# sensing.net
KiCad netlist of a schematic drawn in EAGLE
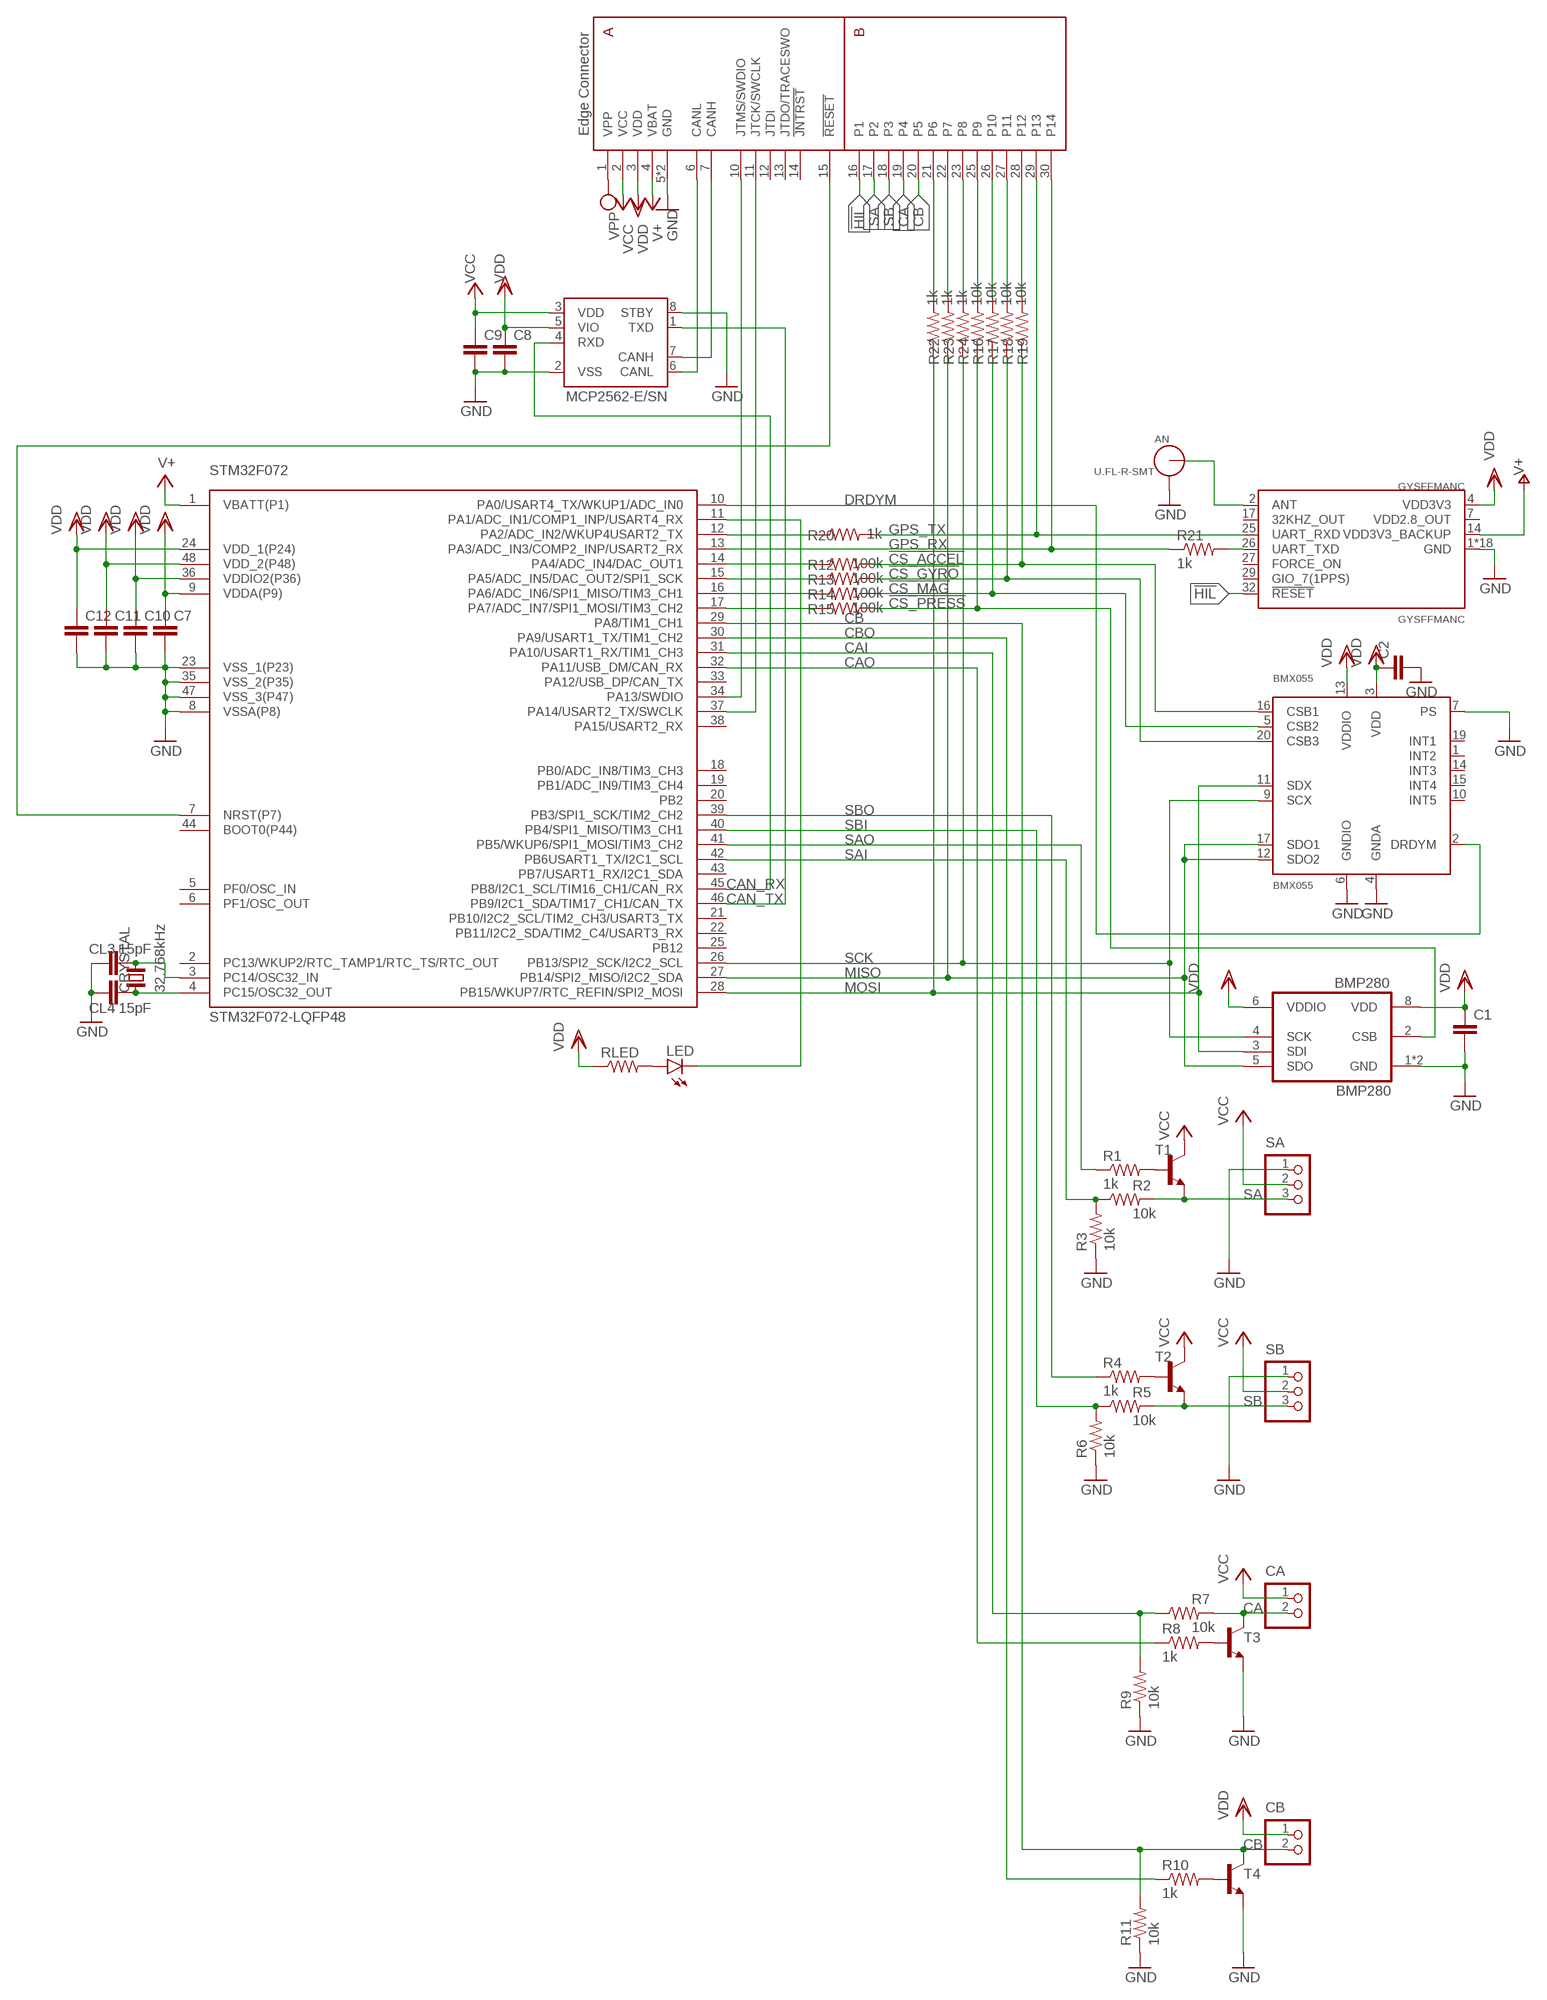
[diagram p0: schematic, sheet 1]

(export (version "E")
  (design (tool "Eeschema 10.0.6"))
  (components
    (comp (ref "AN")
      (value "U.FL-R-SMT")
      (footprint "eagle-import:U.FL_SMT")
      (fields (field (name "MANUFACTURER") "Hirose") (field (name "MPN") "U.FL-R-SMT-1(01)"))
      (libsource (lib "eagle-import") (part "U.FL-R-SMT"))
    )
    (comp (ref "BMP280")
      (value "BMP280")
      (footprint "eagle-import:BMP280")
      (libsource (lib "eagle-import") (part "BMP280"))
    )
    (comp (ref "BMX055")
      (value "BMX055")
      (footprint "eagle-import:BMX055")
      (fields (field (name "DIGI-KEY_PART_NUMBER") "828-1060-1-ND") (field (name "MF") "Bosch Sensortec"))
      (libsource (lib "eagle-import") (part "BMX055"))
    )
    (comp (ref "C1")
      (value "C-EUC0603K")
      (footprint "eagle-import:C0603K")
      (libsource (lib "eagle-import") (part "C-EUC0603K"))
    )
    (comp (ref "C2")
      (value "C-EUC0603K")
      (footprint "eagle-import:C0603K")
      (libsource (lib "eagle-import") (part "C-EUC0603K"))
    )
    (comp (ref "C7")
      (value "C-EUC0603K")
      (footprint "eagle-import:C0603K")
      (libsource (lib "eagle-import") (part "C-EUC0603K"))
    )
    (comp (ref "C8")
      (value "C-EUC0603K")
      (footprint "eagle-import:C0603K")
      (libsource (lib "eagle-import") (part "C-EUC0603K"))
    )
    (comp (ref "C9")
      (value "C-EUC0603K")
      (footprint "eagle-import:C0603K")
      (libsource (lib "eagle-import") (part "C-EUC0603K"))
    )
    (comp (ref "C10")
      (value "C-EUC0603K")
      (footprint "eagle-import:C0603K")
      (libsource (lib "eagle-import") (part "C-EUC0603K"))
    )
    (comp (ref "C11")
      (value "C-EUC0603K")
      (footprint "eagle-import:C0603K")
      (libsource (lib "eagle-import") (part "C-EUC0603K"))
    )
    (comp (ref "C12")
      (value "C-EUC0603K")
      (footprint "eagle-import:C0603K")
      (libsource (lib "eagle-import") (part "C-EUC0603K"))
    )
    (comp (ref "CA")
      (value "S2B-PH-K-S")
      (footprint "eagle-import:S2B-PH-K-S")
      (libsource (lib "eagle-import") (part "S2B-PH-K-S"))
    )
    (comp (ref "CB")
      (value "S2B-PH-K-S")
      (footprint "eagle-import:S2B-PH-K-S")
      (libsource (lib "eagle-import") (part "S2B-PH-K-S"))
    )
    (comp (ref "CL3")
      (value "15pF")
      (footprint "eagle-import:C0603K")
      (libsource (lib "eagle-import") (part "C-EUC0603K"))
    )
    (comp (ref "CL4")
      (value "15pF")
      (footprint "eagle-import:C0603K")
      (libsource (lib "eagle-import") (part "C-EUC0603K"))
    )
    (comp (ref "CRYSTAL")
      (value "32.768kHz")
      (footprint "eagle-import:FC-255")
      (libsource (lib "eagle-import") (part "CRYTALFC-255"))
    )
    (comp (ref "GYSFFMANC")
      (value "GYSFFMANC")
      (footprint "eagle-import:GYSFFMANC")
      (libsource (lib "eagle-import") (part "GYSFFMANC"))
    )
    (comp (ref "LED")
      (value "LEDCHIP-LED0603")
      (footprint "eagle-import:CHIP-LED0603")
      (libsource (lib "eagle-import") (part "LEDCHIP-LED0603"))
    )
    (comp (ref "MCP2562")
      (value "MCP2562-E/SN")
      (footprint "eagle-import:SOIC127P600X175-8N")
      (fields (field (name "MF") "Microchip"))
      (libsource (lib "eagle-import") (part "MCP2562-E/SN"))
    )
    (comp (ref "R1")
      (value "1k")
      (footprint "eagle-import:R0603")
      (libsource (lib "eagle-import") (part "resistor_348_R-US_R0603"))
    )
    (comp (ref "R2")
      (value "10k")
      (footprint "eagle-import:R0603")
      (libsource (lib "eagle-import") (part "resistor_348_R-US_R0603"))
    )
    (comp (ref "R3")
      (value "10k")
      (footprint "eagle-import:R0603")
      (libsource (lib "eagle-import") (part "resistor_348_R-US_R0603"))
    )
    (comp (ref "R4")
      (value "1k")
      (footprint "eagle-import:R0603")
      (libsource (lib "eagle-import") (part "resistor_348_R-US_R0603"))
    )
    (comp (ref "R5")
      (value "10k")
      (footprint "eagle-import:R0603")
      (libsource (lib "eagle-import") (part "resistor_348_R-US_R0603"))
    )
    (comp (ref "R6")
      (value "10k")
      (footprint "eagle-import:R0603")
      (libsource (lib "eagle-import") (part "resistor_348_R-US_R0603"))
    )
    (comp (ref "R7")
      (value "10k")
      (footprint "eagle-import:R0603")
      (libsource (lib "eagle-import") (part "resistor_348_R-US_R0603"))
    )
    (comp (ref "R8")
      (value "1k")
      (footprint "eagle-import:R0603")
      (libsource (lib "eagle-import") (part "resistor_348_R-US_R0603"))
    )
    (comp (ref "R9")
      (value "10k")
      (footprint "eagle-import:R0603")
      (libsource (lib "eagle-import") (part "resistor_348_R-US_R0603"))
    )
    (comp (ref "R10")
      (value "1k")
      (footprint "eagle-import:R0603")
      (libsource (lib "eagle-import") (part "resistor_348_R-US_R0603"))
    )
    (comp (ref "R11")
      (value "10k")
      (footprint "eagle-import:R0603")
      (libsource (lib "eagle-import") (part "resistor_348_R-US_R0603"))
    )
    (comp (ref "R12")
      (value "100k")
      (footprint "eagle-import:R0603")
      (libsource (lib "eagle-import") (part "resistor_348_R-US_R0603"))
    )
    (comp (ref "R13")
      (value "100k")
      (footprint "eagle-import:R0603")
      (libsource (lib "eagle-import") (part "resistor_348_R-US_R0603"))
    )
    (comp (ref "R14")
      (value "100k")
      (footprint "eagle-import:R0603")
      (libsource (lib "eagle-import") (part "resistor_348_R-US_R0603"))
    )
    (comp (ref "R15")
      (value "100k")
      (footprint "eagle-import:R0603")
      (libsource (lib "eagle-import") (part "resistor_348_R-US_R0603"))
    )
    (comp (ref "R16")
      (value "10k")
      (footprint "eagle-import:R0603")
      (libsource (lib "eagle-import") (part "resistor_348_R-US_R0603"))
    )
    (comp (ref "R17")
      (value "10k")
      (footprint "eagle-import:R0603")
      (libsource (lib "eagle-import") (part "resistor_348_R-US_R0603"))
    )
    (comp (ref "R18")
      (value "10k")
      (footprint "eagle-import:R0603")
      (libsource (lib "eagle-import") (part "resistor_348_R-US_R0603"))
    )
    (comp (ref "R19")
      (value "10k")
      (footprint "eagle-import:R0603")
      (libsource (lib "eagle-import") (part "resistor_348_R-US_R0603"))
    )
    (comp (ref "R20")
      (value "1k")
      (footprint "eagle-import:R0603")
      (libsource (lib "eagle-import") (part "resistor_348_R-US_R0603"))
    )
    (comp (ref "R21")
      (value "1k")
      (footprint "eagle-import:R0603")
      (libsource (lib "eagle-import") (part "resistor_348_R-US_R0603"))
    )
    (comp (ref "R22")
      (value "1k")
      (footprint "eagle-import:R0603")
      (libsource (lib "eagle-import") (part "resistor_348_R-US_R0603"))
    )
    (comp (ref "R23")
      (value "1k")
      (footprint "eagle-import:R0603")
      (libsource (lib "eagle-import") (part "resistor_348_R-US_R0603"))
    )
    (comp (ref "R24")
      (value "1k")
      (footprint "eagle-import:R0603")
      (libsource (lib "eagle-import") (part "resistor_348_R-US_R0603"))
    )
    (comp (ref "RLED")
      (value "R-US_R0603")
      (footprint "eagle-import:R0603")
      (libsource (lib "eagle-import") (part "R-US_R0603"))
    )
    (comp (ref "SA")
      (value "S3B-PH-K-S")
      (footprint "eagle-import:S3B-PH-K-S")
      (libsource (lib "eagle-import") (part "S3B-PH-K-S"))
    )
    (comp (ref "SB")
      (value "S3B-PH-K-S")
      (footprint "eagle-import:S3B-PH-K-S")
      (libsource (lib "eagle-import") (part "S3B-PH-K-S"))
    )
    (comp (ref "STM32F072")
      (value "STM32F072-LQFP48")
      (footprint "eagle-import:LQFP48")
      (libsource (lib "eagle-import") (part "STM32F072-LQFP48"))
    )
    (comp (ref "T1")
      (value "BC817-NPN-SOT23-BEC")
      (footprint "eagle-import:SOT23-BEC")
      (libsource (lib "eagle-import") (part "-NPN-SOT23-BECBC817"))
    )
    (comp (ref "T2")
      (value "BC817-NPN-SOT23-BEC")
      (footprint "eagle-import:SOT23-BEC")
      (libsource (lib "eagle-import") (part "-NPN-SOT23-BECBC817"))
    )
    (comp (ref "T3")
      (value "BC817-NPN-SOT23-BEC")
      (footprint "eagle-import:SOT23-BEC")
      (libsource (lib "eagle-import") (part "-NPN-SOT23-BECBC817"))
    )
    (comp (ref "T4")
      (value "BC817-NPN-SOT23-BEC")
      (footprint "eagle-import:SOT23-BEC")
      (libsource (lib "eagle-import") (part "-NPN-SOT23-BECBC817"))
    )
    (comp (ref "U$2")
      (value "EDGE30")
      (footprint "eagle-import:EDGE30")
      (libsource (lib "eagle-import") (part "EDGE30"))
    )
  )
  (nets
    (net (code "1") (name "/CAI") (class "Default")
      (node (ref "R7") (pin "1") (pinfunction "1_1") (pintype "passive"))
      (node (ref "R9") (pin "2") (pinfunction "2_2") (pintype "passive"))
      (node (ref "STM32F072") (pin "31") (pinfunction "PA10/USART1_RX/TIM1_CH3_31") (pintype "bidirectional"))
    )
    (net (code "2") (name "/CAN_RX") (class "Default")
      (node (ref "MCP2562") (pin "4") (pinfunction "RXD_4") (pintype "output"))
      (node (ref "STM32F072") (pin "45") (pinfunction "PB8/I2C1_SCL/TIM16_CH1/CAN_RX_45") (pintype "bidirectional"))
    )
    (net (code "3") (name "/CAN_TX") (class "Default")
      (node (ref "MCP2562") (pin "1") (pinfunction "TXD_1") (pintype "input"))
      (node (ref "STM32F072") (pin "46") (pinfunction "PB9/I2C1_SDA/TIM17_CH1/CAN_TX_46") (pintype "bidirectional"))
    )
    (net (code "4") (name "/CAO") (class "Default")
      (node (ref "R8") (pin "1") (pinfunction "1_1") (pintype "passive"))
      (node (ref "STM32F072") (pin "32") (pinfunction "PA11/USB_DM/CAN_RX_32") (pintype "bidirectional"))
    )
    (net (code "5") (name "/CBO") (class "Default")
      (node (ref "R10") (pin "1") (pinfunction "1_1") (pintype "passive"))
      (node (ref "STM32F072") (pin "30") (pinfunction "PA9/USART1_TX/TIM1_CH2_30") (pintype "bidirectional"))
    )
    (net (code "6") (name "/DRDYM") (class "Default")
      (node (ref "BMX055") (pin "2") (pinfunction "DRDYM_2") (pintype "bidirectional"))
      (node (ref "STM32F072") (pin "10") (pinfunction "PA0/USART4_TX/WKUP1/ADC_IN0_10") (pintype "bidirectional"))
    )
    (net (code "7") (name "/GPS_RX") (class "Default")
      (node (ref "R21") (pin "1") (pinfunction "1_1") (pintype "passive"))
      (node (ref "STM32F072") (pin "13") (pinfunction "PA3/ADC_IN3/COMP2_INP/USART2_RX_13") (pintype "bidirectional"))
      (node (ref "U$2") (pin "30") (pinfunction "P14_30") (pintype "bidirectional"))
    )
    (net (code "8") (name "/GPS_TX") (class "Default")
      (node (ref "GYSFFMANC") (pin "25") (pinfunction "UART_RXD_25") (pintype "input"))
      (node (ref "R20") (pin "2") (pinfunction "2_2") (pintype "passive"))
      (node (ref "U$2") (pin "29") (pinfunction "P13_29") (pintype "bidirectional"))
    )
    (net (code "9") (name "/MISO") (class "Default")
      (node (ref "BMP280") (pin "5") (pinfunction "SDO_5") (pintype "input"))
      (node (ref "BMX055") (pin "12") (pinfunction "SDO2_12") (pintype "bidirectional"))
      (node (ref "BMX055") (pin "17") (pinfunction "SDO1_17") (pintype "bidirectional"))
      (node (ref "R23") (pin "1") (pinfunction "1_1") (pintype "passive"))
      (node (ref "STM32F072") (pin "27") (pinfunction "PB14/SPI2_MISO/I2C2_SDA_27") (pintype "bidirectional"))
    )
    (net (code "10") (name "/MOSI") (class "Default")
      (node (ref "BMP280") (pin "3") (pinfunction "SDI_3") (pintype "bidirectional"))
      (node (ref "BMX055") (pin "11") (pinfunction "SDX_11") (pintype "bidirectional"))
      (node (ref "R22") (pin "1") (pinfunction "1_1") (pintype "passive"))
      (node (ref "STM32F072") (pin "28") (pinfunction "PB15/WKUP7/RTC_REFIN/SPI2_MOSI_28") (pintype "bidirectional"))
    )
    (net (code "11") (name "/SAI") (class "Default")
      (node (ref "R2") (pin "1") (pinfunction "1_1") (pintype "passive"))
      (node (ref "R3") (pin "2") (pinfunction "2_2") (pintype "passive"))
      (node (ref "STM32F072") (pin "42") (pinfunction "PB6USART1_TX/I2C1_SCL_42") (pintype "bidirectional"))
    )
    (net (code "12") (name "/SAO") (class "Default")
      (node (ref "R1") (pin "1") (pinfunction "1_1") (pintype "passive"))
      (node (ref "STM32F072") (pin "41") (pinfunction "PB5/WKUP6/SPI1_MOSI/TIM3_CH2_41") (pintype "bidirectional"))
    )
    (net (code "13") (name "/SBI") (class "Default")
      (node (ref "R5") (pin "1") (pinfunction "1_1") (pintype "passive"))
      (node (ref "R6") (pin "2") (pinfunction "2_2") (pintype "passive"))
      (node (ref "STM32F072") (pin "40") (pinfunction "PB4/SPI1_MISO/TIM3_CH1_40") (pintype "bidirectional"))
    )
    (net (code "14") (name "/SBO") (class "Default")
      (node (ref "R4") (pin "1") (pinfunction "1_1") (pintype "passive"))
      (node (ref "STM32F072") (pin "39") (pinfunction "PB3/SPI1_SCK/TIM2_CH2_39") (pintype "bidirectional"))
    )
    (net (code "15") (name "/SCK") (class "Default")
      (node (ref "BMP280") (pin "4") (pinfunction "SCK_4") (pintype "bidirectional"))
      (node (ref "BMX055") (pin "9") (pinfunction "SCX_9") (pintype "bidirectional"))
      (node (ref "R24") (pin "1") (pinfunction "1_1") (pintype "passive"))
      (node (ref "STM32F072") (pin "26") (pinfunction "PB13/SPI2_SCK/I2C2_SCL_26") (pintype "bidirectional"))
    )
    (net (code "16") (name "/VDD2.8_OUT") (class "Default")
      (node (ref "GYSFFMANC") (pin "7") (pinfunction "VDD2.8_OUT_7") (pintype "power_in"))
    )
    (net (code "17") (name "/~{CS_ACCEL}") (class "Default")
      (node (ref "BMX055") (pin "16") (pinfunction "CSB1_16") (pintype "bidirectional"))
      (node (ref "R12") (pin "2") (pinfunction "2_2") (pintype "passive"))
      (node (ref "R19") (pin "1") (pinfunction "1_1") (pintype "passive"))
    )
    (net (code "18") (name "/~{CS_GYRO}") (class "Default")
      (node (ref "BMX055") (pin "20") (pinfunction "CSB3_20") (pintype "bidirectional"))
      (node (ref "R13") (pin "2") (pinfunction "2_2") (pintype "passive"))
      (node (ref "R18") (pin "1") (pinfunction "1_1") (pintype "passive"))
    )
    (net (code "19") (name "/~{CS_MAG}") (class "Default")
      (node (ref "BMX055") (pin "5") (pinfunction "CSB2_5") (pintype "bidirectional"))
      (node (ref "R14") (pin "2") (pinfunction "2_2") (pintype "passive"))
      (node (ref "R17") (pin "1") (pinfunction "1_1") (pintype "passive"))
    )
    (net (code "20") (name "/~{CS_PRESS}") (class "Default")
      (node (ref "BMP280") (pin "2") (pinfunction "CSB_2") (pintype "input"))
      (node (ref "R15") (pin "2") (pinfunction "2_2") (pintype "passive"))
      (node (ref "R16") (pin "1") (pinfunction "1_1") (pintype "passive"))
    )
    (net (code "21") (name "/~{HIL}") (class "Default")
      (node (ref "GYSFFMANC") (pin "32") (pinfunction "~{RESET}_32") (pintype "input"))
      (node (ref "U$2") (pin "16") (pinfunction "P1_16") (pintype "bidirectional"))
    )
    (net (code "22") (name "CA") (class "Default")
      (node (ref "CA") (pin "2") (pinfunction "2_2") (pintype "passive"))
      (node (ref "R7") (pin "2") (pinfunction "2_2") (pintype "passive"))
      (node (ref "T3") (pin "C") (pinfunction "C_C") (pintype "passive"))
      (node (ref "U$2") (pin "19") (pinfunction "P4_19") (pintype "bidirectional"))
    )
    (net (code "23") (name "CB") (class "Default")
      (node (ref "CB") (pin "2") (pinfunction "2_2") (pintype "passive"))
      (node (ref "R11") (pin "2") (pinfunction "2_2") (pintype "passive"))
      (node (ref "STM32F072") (pin "29") (pinfunction "PA8/TIM1_CH1_29") (pintype "bidirectional"))
      (node (ref "T4") (pin "C") (pinfunction "C_C") (pintype "passive"))
      (node (ref "U$2") (pin "20") (pinfunction "P5_20") (pintype "bidirectional"))
    )
    (net (code "24") (name "GND") (class "Default")
      (node (ref "AN") (pin "GND1") (pinfunction "P$2_GND1") (pintype "bidirectional"))
      (node (ref "AN") (pin "GND2") (pinfunction "P$2_GND2") (pintype "bidirectional"))
      (node (ref "BMP280") (pin "1") (pinfunction "GND_1") (pintype "power_in"))
      (node (ref "BMP280") (pin "7") (pinfunction "GND_7") (pintype "power_in"))
      (node (ref "BMX055") (pin "4") (pinfunction "GNDA_4") (pintype "bidirectional"))
      (node (ref "BMX055") (pin "6") (pinfunction "GNDIO_6") (pintype "bidirectional"))
      (node (ref "BMX055") (pin "7") (pinfunction "PS_7") (pintype "bidirectional"))
      (node (ref "C1") (pin "2") (pinfunction "2_2") (pintype "passive"))
      (node (ref "C10") (pin "2") (pinfunction "2_2") (pintype "passive"))
      (node (ref "C11") (pin "2") (pinfunction "2_2") (pintype "passive"))
      (node (ref "C12") (pin "2") (pinfunction "2_2") (pintype "passive"))
      (node (ref "C2") (pin "2") (pinfunction "2_2") (pintype "passive"))
      (node (ref "C7") (pin "2") (pinfunction "2_2") (pintype "passive"))
      (node (ref "C8") (pin "2") (pinfunction "2_2") (pintype "passive"))
      (node (ref "C9") (pin "2") (pinfunction "2_2") (pintype "passive"))
      (node (ref "CL3") (pin "1") (pinfunction "1_1") (pintype "passive"))
      (node (ref "CL4") (pin "1") (pinfunction "1_1") (pintype "passive"))
      (node (ref "GYSFFMANC") (pin "1") (pinfunction "GND_1") (pintype "power_in"))
      (node (ref "GYSFFMANC") (pin "10") (pinfunction "GND_10") (pintype "power_in"))
      (node (ref "GYSFFMANC") (pin "12") (pinfunction "GND_12") (pintype "power_in"))
      (node (ref "GYSFFMANC") (pin "22") (pinfunction "GND_22") (pintype "power_in"))
      (node (ref "GYSFFMANC") (pin "3") (pinfunction "GND_3") (pintype "power_in"))
      (node (ref "GYSFFMANC") (pin "33") (pinfunction "GND_33") (pintype "power_in"))
      (node (ref "GYSFFMANC") (pin "36") (pinfunction "GND_36") (pintype "power_in"))
      (node (ref "GYSFFMANC") (pin "37") (pinfunction "GND_37") (pintype "power_in"))
      (node (ref "GYSFFMANC") (pin "38") (pinfunction "GND_38") (pintype "power_in"))
      (node (ref "GYSFFMANC") (pin "39") (pinfunction "GND_39") (pintype "power_in"))
      (node (ref "GYSFFMANC") (pin "40") (pinfunction "GND_40") (pintype "power_in"))
      (node (ref "GYSFFMANC") (pin "41") (pinfunction "GND_41") (pintype "power_in"))
      (node (ref "GYSFFMANC") (pin "42") (pinfunction "GND_42") (pintype "power_in"))
      (node (ref "GYSFFMANC") (pin "43") (pinfunction "GND_43") (pintype "power_in"))
      (node (ref "GYSFFMANC") (pin "44") (pinfunction "GND_44") (pintype "power_in"))
      (node (ref "GYSFFMANC") (pin "45") (pinfunction "GND_45") (pintype "power_in"))
      (node (ref "GYSFFMANC") (pin "46") (pinfunction "GND_46") (pintype "power_in"))
      (node (ref "GYSFFMANC") (pin "8") (pinfunction "GND_8") (pintype "power_in"))
      (node (ref "MCP2562") (pin "2") (pinfunction "VSS_2") (pintype "power_in"))
      (node (ref "MCP2562") (pin "8") (pinfunction "STBY_8") (pintype "input"))
      (node (ref "R11") (pin "1") (pinfunction "1_1") (pintype "passive"))
      (node (ref "R3") (pin "1") (pinfunction "1_1") (pintype "passive"))
      (node (ref "R6") (pin "1") (pinfunction "1_1") (pintype "passive"))
      (node (ref "R9") (pin "1") (pinfunction "1_1") (pintype "passive"))
      (node (ref "SA") (pin "1") (pinfunction "1_1") (pintype "passive"))
      (node (ref "SB") (pin "1") (pinfunction "1_1") (pintype "passive"))
      (node (ref "STM32F072") (pin "23") (pinfunction "VSS_1(P23)_23") (pintype "bidirectional"))
      (node (ref "STM32F072") (pin "35") (pinfunction "VSS_2(P35)_35") (pintype "bidirectional"))
      (node (ref "STM32F072") (pin "47") (pinfunction "VSS_3(P47)_47") (pintype "bidirectional"))
      (node (ref "STM32F072") (pin "8") (pinfunction "VSSA(P8)_8") (pintype "bidirectional"))
      (node (ref "T3") (pin "E") (pinfunction "E_E") (pintype "passive"))
      (node (ref "T4") (pin "E") (pinfunction "E_E") (pintype "passive"))
      (node (ref "U$2") (pin "5") (pinfunction "GND_5") (pintype "power_in"))
      (node (ref "U$2") (pin "8") (pinfunction "GND_8") (pintype "power_in"))
    )
    (net (code "25") (name "Net-(AN-ANT)") (class "Default")
      (node (ref "AN") (pin "SIG") (pinfunction "ANT_SIG") (pintype "bidirectional"))
      (node (ref "GYSFFMANC") (pin "2") (pinfunction "ANT_2") (pintype "input"))
    )
    (net (code "26") (name "Net-(GYSFFMANC-UART_TXD)") (class "Default")
      (node (ref "GYSFFMANC") (pin "26") (pinfunction "UART_TXD_26") (pintype "output"))
      (node (ref "R21") (pin "2") (pinfunction "2_2") (pintype "passive"))
    )
    (net (code "27") (name "Net-(LED-PadA)") (class "Default")
      (node (ref "LED") (pin "A") (pinfunction "A_A") (pintype "passive"))
      (node (ref "RLED") (pin "2") (pinfunction "2_2") (pintype "passive"))
    )
    (net (code "28") (name "Net-(MCP2562-CANH)") (class "Default")
      (node (ref "MCP2562") (pin "7") (pinfunction "CANH_7") (pintype "input"))
      (node (ref "U$2") (pin "7") (pinfunction "CANH_7") (pintype "bidirectional"))
    )
    (net (code "29") (name "Net-(MCP2562-CANL)") (class "Default")
      (node (ref "MCP2562") (pin "6") (pinfunction "CANL_6") (pintype "input"))
      (node (ref "U$2") (pin "6") (pinfunction "CANL_6") (pintype "bidirectional"))
    )
    (net (code "30") (name "Net-(R1-Pad2)") (class "Default")
      (node (ref "R1") (pin "2") (pinfunction "2_2") (pintype "passive"))
      (node (ref "T1") (pin "B") (pinfunction "B_B") (pintype "passive"))
    )
    (net (code "31") (name "Net-(R4-Pad2)") (class "Default")
      (node (ref "R4") (pin "2") (pinfunction "2_2") (pintype "passive"))
      (node (ref "T2") (pin "B") (pinfunction "B_B") (pintype "passive"))
    )
    (net (code "32") (name "Net-(R8-Pad2)") (class "Default")
      (node (ref "R8") (pin "2") (pinfunction "2_2") (pintype "passive"))
      (node (ref "T3") (pin "B") (pinfunction "B_B") (pintype "passive"))
    )
    (net (code "33") (name "Net-(R10-Pad2)") (class "Default")
      (node (ref "R10") (pin "2") (pinfunction "2_2") (pintype "passive"))
      (node (ref "T4") (pin "B") (pinfunction "B_B") (pintype "passive"))
    )
    (net (code "34") (name "Net-(STM32F072-NRST(P7))") (class "Default")
      (node (ref "STM32F072") (pin "7") (pinfunction "NRST(P7)_7") (pintype "bidirectional"))
      (node (ref "U$2") (pin "15") (pinfunction "~{RESET}_15") (pintype "bidirectional"))
    )
    (net (code "35") (name "Net-(STM32F072-PA1{slash}ADC_IN1{slash}COMP1_INP{slash}USART4_RX)") (class "Default")
      (node (ref "LED") (pin "C") (pinfunction "C_C") (pintype "passive"))
      (node (ref "STM32F072") (pin "11") (pinfunction "PA1/ADC_IN1/COMP1_INP/USART4_RX_11") (pintype "bidirectional"))
    )
    (net (code "36") (name "Net-(STM32F072-PA2{slash}ADC_IN2{slash}WKUP4USART2_TX)") (class "Default")
      (node (ref "R20") (pin "1") (pinfunction "1_1") (pintype "passive"))
      (node (ref "STM32F072") (pin "12") (pinfunction "PA2/ADC_IN2/WKUP4USART2_TX_12") (pintype "bidirectional"))
    )
    (net (code "37") (name "Net-(STM32F072-PA4{slash}ADC_IN4{slash}DAC_OUT1)") (class "Default")
      (node (ref "R12") (pin "1") (pinfunction "1_1") (pintype "passive"))
      (node (ref "STM32F072") (pin "14") (pinfunction "PA4/ADC_IN4/DAC_OUT1_14") (pintype "bidirectional"))
    )
    (net (code "38") (name "Net-(STM32F072-PA5{slash}ADC_IN5{slash}DAC_OUT2{slash}SPI1_SCK)") (class "Default")
      (node (ref "R13") (pin "1") (pinfunction "1_1") (pintype "passive"))
      (node (ref "STM32F072") (pin "15") (pinfunction "PA5/ADC_IN5/DAC_OUT2/SPI1_SCK_15") (pintype "bidirectional"))
    )
    (net (code "39") (name "Net-(STM32F072-PA6{slash}ADC_IN6{slash}SPI1_MISO{slash}TIM3_CH1)") (class "Default")
      (node (ref "R14") (pin "1") (pinfunction "1_1") (pintype "passive"))
      (node (ref "STM32F072") (pin "16") (pinfunction "PA6/ADC_IN6/SPI1_MISO/TIM3_CH1_16") (pintype "bidirectional"))
    )
    (net (code "40") (name "Net-(STM32F072-PA7{slash}ADC_IN7{slash}SPI1_MOSI{slash}TIM3_CH2)") (class "Default")
      (node (ref "R15") (pin "1") (pinfunction "1_1") (pintype "passive"))
      (node (ref "STM32F072") (pin "17") (pinfunction "PA7/ADC_IN7/SPI1_MOSI/TIM3_CH2_17") (pintype "bidirectional"))
    )
    (net (code "41") (name "Net-(STM32F072-PA13{slash}SWDIO)") (class "Default")
      (node (ref "STM32F072") (pin "34") (pinfunction "PA13/SWDIO_34") (pintype "bidirectional"))
      (node (ref "U$2") (pin "10") (pinfunction "JTMS/SWDIO_10") (pintype "bidirectional"))
    )
    (net (code "42") (name "Net-(STM32F072-PA14{slash}USART2_TX{slash}SWCLK)") (class "Default")
      (node (ref "STM32F072") (pin "37") (pinfunction "PA14/USART2_TX/SWCLK_37") (pintype "bidirectional"))
      (node (ref "U$2") (pin "11") (pinfunction "JTCK/SWCLK_11") (pintype "bidirectional"))
    )
    (net (code "43") (name "Net-(STM32F072-PC14{slash}OSC32_IN)") (class "Default")
      (node (ref "CL3") (pin "2") (pinfunction "2_2") (pintype "passive"))
      (node (ref "CRYSTAL") (pin "2") (pinfunction "2_2") (pintype "passive"))
      (node (ref "STM32F072") (pin "3") (pinfunction "PC14/OSC32_IN_3") (pintype "bidirectional"))
    )
    (net (code "44") (name "Net-(STM32F072-PC15{slash}OSC32_OUT)") (class "Default")
      (node (ref "CL4") (pin "2") (pinfunction "2_2") (pintype "passive"))
      (node (ref "CRYSTAL") (pin "1") (pinfunction "1_1") (pintype "passive"))
      (node (ref "STM32F072") (pin "4") (pinfunction "PC15/OSC32_OUT_4") (pintype "bidirectional"))
    )
    (net (code "45") (name "Net-(U$2-P6)") (class "Default")
      (node (ref "R22") (pin "2") (pinfunction "2_2") (pintype "passive"))
      (node (ref "U$2") (pin "21") (pinfunction "P6_21") (pintype "bidirectional"))
    )
    (net (code "46") (name "Net-(U$2-P7)") (class "Default")
      (node (ref "R23") (pin "2") (pinfunction "2_2") (pintype "passive"))
      (node (ref "U$2") (pin "22") (pinfunction "P7_22") (pintype "bidirectional"))
    )
    (net (code "47") (name "Net-(U$2-P8)") (class "Default")
      (node (ref "R24") (pin "2") (pinfunction "2_2") (pintype "passive"))
      (node (ref "U$2") (pin "23") (pinfunction "P8_23") (pintype "bidirectional"))
    )
    (net (code "48") (name "Net-(U$2-P9)") (class "Default")
      (node (ref "R16") (pin "2") (pinfunction "2_2") (pintype "passive"))
      (node (ref "U$2") (pin "25") (pinfunction "P9_25") (pintype "bidirectional"))
    )
    (net (code "49") (name "Net-(U$2-P10)") (class "Default")
      (node (ref "R17") (pin "2") (pinfunction "2_2") (pintype "passive"))
      (node (ref "U$2") (pin "26") (pinfunction "P10_26") (pintype "bidirectional"))
    )
    (net (code "50") (name "Net-(U$2-P11)") (class "Default")
      (node (ref "R18") (pin "2") (pinfunction "2_2") (pintype "passive"))
      (node (ref "U$2") (pin "27") (pinfunction "P11_27") (pintype "bidirectional"))
    )
    (net (code "51") (name "Net-(U$2-P12)") (class "Default")
      (node (ref "R19") (pin "2") (pinfunction "2_2") (pintype "passive"))
      (node (ref "U$2") (pin "28") (pinfunction "P12_28") (pintype "bidirectional"))
    )
    (net (code "52") (name "SA") (class "Default")
      (node (ref "R2") (pin "2") (pinfunction "2_2") (pintype "passive"))
      (node (ref "SA") (pin "3") (pinfunction "3_3") (pintype "passive"))
      (node (ref "T1") (pin "E") (pinfunction "E_E") (pintype "passive"))
      (node (ref "U$2") (pin "17") (pinfunction "P2_17") (pintype "bidirectional"))
    )
    (net (code "53") (name "SB") (class "Default")
      (node (ref "R5") (pin "2") (pinfunction "2_2") (pintype "passive"))
      (node (ref "SB") (pin "3") (pinfunction "3_3") (pintype "passive"))
      (node (ref "T2") (pin "E") (pinfunction "E_E") (pintype "passive"))
      (node (ref "U$2") (pin "18") (pinfunction "P3_18") (pintype "bidirectional"))
    )
    (net (code "54") (name "V+") (class "Default")
      (node (ref "GYSFFMANC") (pin "14") (pinfunction "VDD3V3_BACKUP_14") (pintype "power_in"))
      (node (ref "STM32F072") (pin "1") (pinfunction "VBATT(P1)_1") (pintype "bidirectional"))
      (node (ref "U$2") (pin "4") (pinfunction "VBAT_4") (pintype "power_in"))
    )
    (net (code "55") (name "VCC") (class "Default")
      (node (ref "C9") (pin "1") (pinfunction "1_1") (pintype "passive"))
      (node (ref "CA") (pin "1") (pinfunction "1_1") (pintype "passive"))
      (node (ref "MCP2562") (pin "3") (pinfunction "VDD_3") (pintype "power_in"))
      (node (ref "SA") (pin "2") (pinfunction "2_2") (pintype "passive"))
      (node (ref "SB") (pin "2") (pinfunction "2_2") (pintype "passive"))
      (node (ref "T1") (pin "C") (pinfunction "C_C") (pintype "passive"))
      (node (ref "T2") (pin "C") (pinfunction "C_C") (pintype "passive"))
      (node (ref "U$2") (pin "2") (pinfunction "VCC_2") (pintype "power_in"))
    )
    (net (code "56") (name "VDD") (class "Default")
      (node (ref "BMP280") (pin "6") (pinfunction "VDDIO_6") (pintype "power_in"))
      (node (ref "BMP280") (pin "8") (pinfunction "VDD_8") (pintype "power_in"))
      (node (ref "BMX055") (pin "13") (pinfunction "VDDIO_13") (pintype "bidirectional"))
      (node (ref "BMX055") (pin "3") (pinfunction "VDD_3") (pintype "bidirectional"))
      (node (ref "C1") (pin "1") (pinfunction "1_1") (pintype "passive"))
      (node (ref "C10") (pin "1") (pinfunction "1_1") (pintype "passive"))
      (node (ref "C11") (pin "1") (pinfunction "1_1") (pintype "passive"))
      (node (ref "C12") (pin "1") (pinfunction "1_1") (pintype "passive"))
      (node (ref "C2") (pin "1") (pinfunction "1_1") (pintype "passive"))
      (node (ref "C7") (pin "1") (pinfunction "1_1") (pintype "passive"))
      (node (ref "C8") (pin "1") (pinfunction "1_1") (pintype "passive"))
      (node (ref "CB") (pin "1") (pinfunction "1_1") (pintype "passive"))
      (node (ref "GYSFFMANC") (pin "4") (pinfunction "VDD3V3_4") (pintype "power_in"))
      (node (ref "MCP2562") (pin "5") (pinfunction "VIO_5") (pintype "power_in"))
      (node (ref "RLED") (pin "1") (pinfunction "1_1") (pintype "passive"))
      (node (ref "STM32F072") (pin "24") (pinfunction "VDD_1(P24)_24") (pintype "bidirectional"))
      (node (ref "STM32F072") (pin "36") (pinfunction "VDDIO2(P36)_36") (pintype "bidirectional"))
      (node (ref "STM32F072") (pin "48") (pinfunction "VDD_2(P48)_48") (pintype "bidirectional"))
      (node (ref "STM32F072") (pin "9") (pinfunction "VDDA(P9)_9") (pintype "bidirectional"))
      (node (ref "U$2") (pin "3") (pinfunction "VDD_3") (pintype "power_in"))
    )
    (net (code "57") (name "VPP") (class "Default")
      (node (ref "U$2") (pin "1") (pinfunction "VPP_1") (pintype "power_in"))
    )
    (net (code "58") (name "unconnected-(BMX055-INT1-Pad19)") (class "Default")
      (node (ref "BMX055") (pin "19") (pinfunction "INT1_19") (pintype "bidirectional"))
    )
    (net (code "59") (name "unconnected-(BMX055-INT2-Pad1)") (class "Default")
      (node (ref "BMX055") (pin "1") (pinfunction "INT2_1") (pintype "bidirectional"))
    )
    (net (code "60") (name "unconnected-(BMX055-INT3-Pad14)") (class "Default")
      (node (ref "BMX055") (pin "14") (pinfunction "INT3_14") (pintype "bidirectional"))
    )
    (net (code "61") (name "unconnected-(BMX055-INT4-Pad15)") (class "Default")
      (node (ref "BMX055") (pin "15") (pinfunction "INT4_15") (pintype "bidirectional"))
    )
    (net (code "62") (name "unconnected-(BMX055-INT5-Pad10)") (class "Default")
      (node (ref "BMX055") (pin "10") (pinfunction "INT5_10") (pintype "bidirectional"))
    )
    (net (code "63") (name "unconnected-(GYSFFMANC-32KHZ_OUT-Pad17)") (class "Default")
      (node (ref "GYSFFMANC") (pin "17") (pinfunction "32KHZ_OUT_17") (pintype "output"))
    )
    (net (code "64") (name "unconnected-(GYSFFMANC-FORCE_ON-Pad27)") (class "Default")
      (node (ref "GYSFFMANC") (pin "27") (pinfunction "FORCE_ON_27") (pintype "input"))
    )
    (net (code "65") (name "unconnected-(GYSFFMANC-GIO_7(1PPS)-Pad29)") (class "Default")
      (node (ref "GYSFFMANC") (pin "29") (pinfunction "GIO_7(1PPS)_29") (pintype "bidirectional"))
    )
    (net (code "66") (name "unconnected-(STM32F072-BOOT0(P44)-Pad44)") (class "Default")
      (node (ref "STM32F072") (pin "44") (pinfunction "BOOT0(P44)_44") (pintype "bidirectional"))
    )
    (net (code "67") (name "unconnected-(STM32F072-PA12{slash}USB_DP{slash}CAN_TX-Pad33)") (class "Default")
      (node (ref "STM32F072") (pin "33") (pinfunction "PA12/USB_DP/CAN_TX_33") (pintype "bidirectional"))
    )
    (net (code "68") (name "unconnected-(STM32F072-PA15{slash}USART2_RX-Pad38)") (class "Default")
      (node (ref "STM32F072") (pin "38") (pinfunction "PA15/USART2_RX_38") (pintype "bidirectional"))
    )
    (net (code "69") (name "unconnected-(STM32F072-PB0{slash}ADC_IN8{slash}TIM3_CH3-Pad18)") (class "Default")
      (node (ref "STM32F072") (pin "18") (pinfunction "PB0/ADC_IN8/TIM3_CH3_18") (pintype "bidirectional"))
    )
    (net (code "70") (name "unconnected-(STM32F072-PB1{slash}ADC_IN9{slash}TIM3_CH4-Pad19)") (class "Default")
      (node (ref "STM32F072") (pin "19") (pinfunction "PB1/ADC_IN9/TIM3_CH4_19") (pintype "bidirectional"))
    )
    (net (code "71") (name "unconnected-(STM32F072-PB2-Pad20)") (class "Default")
      (node (ref "STM32F072") (pin "20") (pinfunction "PB2_20") (pintype "bidirectional"))
    )
    (net (code "72") (name "unconnected-(STM32F072-PB7{slash}USART1_RX{slash}I2C1_SDA-Pad43)") (class "Default")
      (node (ref "STM32F072") (pin "43") (pinfunction "PB7/USART1_RX/I2C1_SDA_43") (pintype "bidirectional"))
    )
    (net (code "73") (name "unconnected-(STM32F072-PB10{slash}I2C2_SCL{slash}TIM2_CH3{slash}USART3_TX-Pad21)") (class "Default")
      (node (ref "STM32F072") (pin "21") (pinfunction "PB10/I2C2_SCL/TIM2_CH3/USART3_TX_21") (pintype "bidirectional"))
    )
    (net (code "74") (name "unconnected-(STM32F072-PB11{slash}I2C2_SDA{slash}TIM2_C4{slash}USART3_RX-Pad22)") (class "Default")
      (node (ref "STM32F072") (pin "22") (pinfunction "PB11/I2C2_SDA/TIM2_C4/USART3_RX_22") (pintype "bidirectional"))
    )
    (net (code "75") (name "unconnected-(STM32F072-PB12-Pad25)") (class "Default")
      (node (ref "STM32F072") (pin "25") (pinfunction "PB12_25") (pintype "bidirectional"))
    )
    (net (code "76") (name "unconnected-(STM32F072-PC13{slash}WKUP2{slash}RTC_TAMP1{slash}RTC_TS{slash}RTC_OUT-Pad2)") (class "Default")
      (node (ref "STM32F072") (pin "2") (pinfunction "PC13/WKUP2/RTC_TAMP1/RTC_TS/RTC_OUT_2") (pintype "bidirectional"))
    )
    (net (code "77") (name "unconnected-(STM32F072-PF0{slash}OSC_IN-Pad5)") (class "Default")
      (node (ref "STM32F072") (pin "5") (pinfunction "PF0/OSC_IN_5") (pintype "bidirectional"))
    )
    (net (code "78") (name "unconnected-(STM32F072-PF1{slash}OSC_OUT-Pad6)") (class "Default")
      (node (ref "STM32F072") (pin "6") (pinfunction "PF1/OSC_OUT_6") (pintype "bidirectional"))
    )
    (net (code "79") (name "unconnected-(U$2-JTDI-Pad12)") (class "Default")
      (node (ref "U$2") (pin "12") (pinfunction "JTDI_12") (pintype "bidirectional"))
    )
    (net (code "80") (name "unconnected-(U$2-JTDO{slash}TRACESWO-Pad13)") (class "Default")
      (node (ref "U$2") (pin "13") (pinfunction "JTDO/TRACESWO_13") (pintype "bidirectional"))
    )
    (net (code "81") (name "unconnected-(U$2-~{JNTRST}-Pad14)") (class "Default")
      (node (ref "U$2") (pin "14") (pinfunction "~{JNTRST}_14") (pintype "bidirectional"))
    )
  )
)
